# led.net
KiCad netlist of a schematic drawn in EAGLE
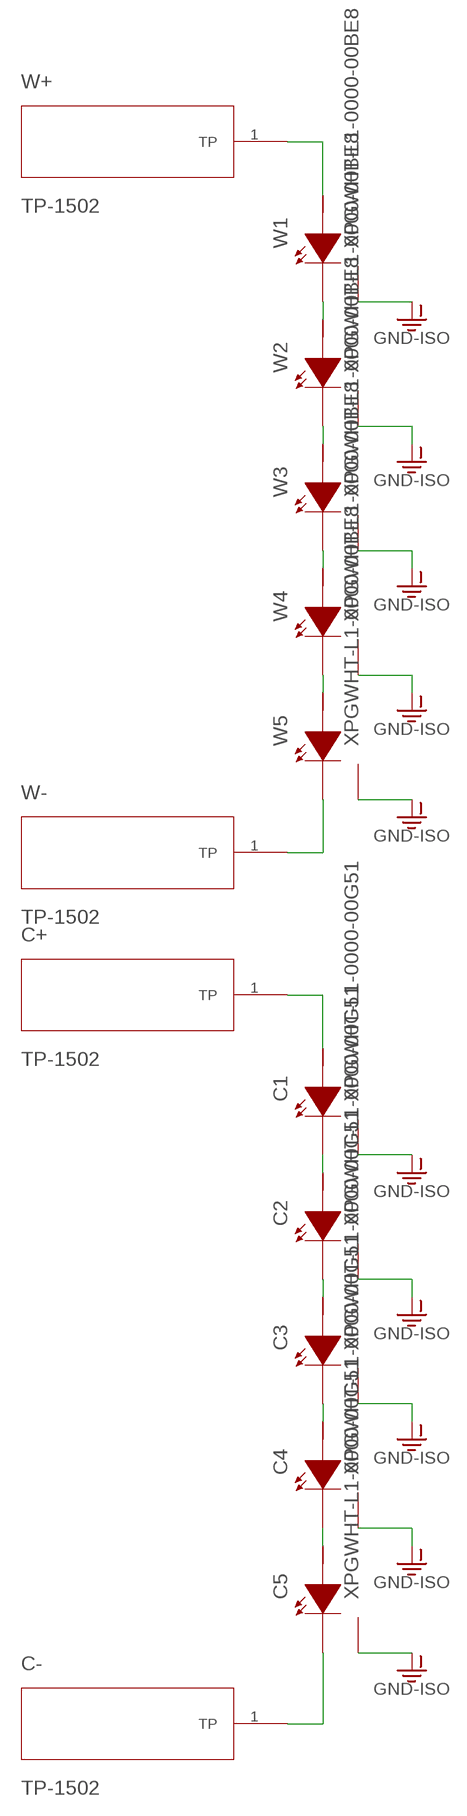
[diagram p0: schematic, sheet 1]

(export (version "E")
  (design (tool "Eeschema 10.0.6"))
  (components
    (comp (ref "C+")
      (value "TP-1502")
      (footprint "eagle-import:TP-1502")
      (libsource (lib "eagle-import") (part "TP-1502"))
    )
    (comp (ref "C-")
      (value "TP-1502")
      (footprint "eagle-import:TP-1502")
      (libsource (lib "eagle-import") (part "TP-1502"))
    )
    (comp (ref "C1")
      (value "XPGWHT-L1-0000-00G51")
      (footprint "eagle-import:XLAMP-XPG")
      (fields (field (name "DIGIKEY_PART_NUMBER") "XPGWHT-L1-0000-00G51CT-ND"))
      (libsource (lib "eagle-import") (part "XPGWHT-L1-0000-00G51"))
    )
    (comp (ref "C2")
      (value "XPGWHT-L1-0000-00G51")
      (footprint "eagle-import:XLAMP-XPG")
      (fields (field (name "DIGIKEY_PART_NUMBER") "XPGWHT-L1-0000-00G51CT-ND"))
      (libsource (lib "eagle-import") (part "XPGWHT-L1-0000-00G51"))
    )
    (comp (ref "C3")
      (value "XPGWHT-L1-0000-00G51")
      (footprint "eagle-import:XLAMP-XPG")
      (fields (field (name "DIGIKEY_PART_NUMBER") "XPGWHT-L1-0000-00G51CT-ND"))
      (libsource (lib "eagle-import") (part "XPGWHT-L1-0000-00G51"))
    )
    (comp (ref "C4")
      (value "XPGWHT-L1-0000-00G51")
      (footprint "eagle-import:XLAMP-XPG")
      (fields (field (name "DIGIKEY_PART_NUMBER") "XPGWHT-L1-0000-00G51CT-ND"))
      (libsource (lib "eagle-import") (part "XPGWHT-L1-0000-00G51"))
    )
    (comp (ref "C5")
      (value "XPGWHT-L1-0000-00G51")
      (footprint "eagle-import:XLAMP-XPG")
      (fields (field (name "DIGIKEY_PART_NUMBER") "XPGWHT-L1-0000-00G51CT-ND"))
      (libsource (lib "eagle-import") (part "XPGWHT-L1-0000-00G51"))
    )
    (comp (ref "W+")
      (value "TP-1502")
      (footprint "eagle-import:TP-1502")
      (libsource (lib "eagle-import") (part "TP-1502"))
    )
    (comp (ref "W-")
      (value "TP-1502")
      (footprint "eagle-import:TP-1502")
      (libsource (lib "eagle-import") (part "TP-1502"))
    )
    (comp (ref "W1")
      (value "XPGWHT-L1-0000-00BE8")
      (footprint "eagle-import:XLAMP-XPG")
      (fields (field (name "DIGIKEY_PART_NUMBER") "XPGWHT-L1-0000-00BE8CT-ND"))
      (libsource (lib "eagle-import") (part "XPGWHT-L1-0000-00BE8"))
    )
    (comp (ref "W2")
      (value "XPGWHT-L1-0000-00BE8")
      (footprint "eagle-import:XLAMP-XPG")
      (fields (field (name "DIGIKEY_PART_NUMBER") "XPGWHT-L1-0000-00BE8CT-ND"))
      (libsource (lib "eagle-import") (part "XPGWHT-L1-0000-00BE8"))
    )
    (comp (ref "W3")
      (value "XPGWHT-L1-0000-00BE8")
      (footprint "eagle-import:XLAMP-XPG")
      (fields (field (name "DIGIKEY_PART_NUMBER") "XPGWHT-L1-0000-00BE8CT-ND"))
      (libsource (lib "eagle-import") (part "XPGWHT-L1-0000-00BE8"))
    )
    (comp (ref "W4")
      (value "XPGWHT-L1-0000-00BE8")
      (footprint "eagle-import:XLAMP-XPG")
      (fields (field (name "DIGIKEY_PART_NUMBER") "XPGWHT-L1-0000-00BE8CT-ND"))
      (libsource (lib "eagle-import") (part "XPGWHT-L1-0000-00BE8"))
    )
    (comp (ref "W5")
      (value "XPGWHT-L1-0000-00BE8")
      (footprint "eagle-import:XLAMP-XPG")
      (fields (field (name "DIGIKEY_PART_NUMBER") "XPGWHT-L1-0000-00BE8CT-ND"))
      (libsource (lib "eagle-import") (part "XPGWHT-L1-0000-00BE8"))
    )
  )
  (nets
    (net (code "1") (name "GND-ISO") (class "Default")
      (node (ref "C1") (pin "GND") (pinfunction "GND_GND") (pintype "passive"))
      (node (ref "C1") (pin "P$1") (pinfunction "GND_P$1") (pintype "passive"))
      (node (ref "C1") (pin "P$2") (pinfunction "GND_P$2") (pintype "passive"))
      (node (ref "C1") (pin "P$3") (pinfunction "GND_P$3") (pintype "passive"))
      (node (ref "C2") (pin "GND") (pinfunction "GND_GND") (pintype "passive"))
      (node (ref "C2") (pin "P$1") (pinfunction "GND_P$1") (pintype "passive"))
      (node (ref "C2") (pin "P$2") (pinfunction "GND_P$2") (pintype "passive"))
      (node (ref "C2") (pin "P$3") (pinfunction "GND_P$3") (pintype "passive"))
      (node (ref "C3") (pin "GND") (pinfunction "GND_GND") (pintype "passive"))
      (node (ref "C3") (pin "P$1") (pinfunction "GND_P$1") (pintype "passive"))
      (node (ref "C3") (pin "P$2") (pinfunction "GND_P$2") (pintype "passive"))
      (node (ref "C3") (pin "P$3") (pinfunction "GND_P$3") (pintype "passive"))
      (node (ref "C4") (pin "GND") (pinfunction "GND_GND") (pintype "passive"))
      (node (ref "C4") (pin "P$1") (pinfunction "GND_P$1") (pintype "passive"))
      (node (ref "C4") (pin "P$2") (pinfunction "GND_P$2") (pintype "passive"))
      (node (ref "C4") (pin "P$3") (pinfunction "GND_P$3") (pintype "passive"))
      (node (ref "C5") (pin "GND") (pinfunction "GND_GND") (pintype "passive"))
      (node (ref "C5") (pin "P$1") (pinfunction "GND_P$1") (pintype "passive"))
      (node (ref "C5") (pin "P$2") (pinfunction "GND_P$2") (pintype "passive"))
      (node (ref "C5") (pin "P$3") (pinfunction "GND_P$3") (pintype "passive"))
      (node (ref "W1") (pin "GND") (pinfunction "GND_GND") (pintype "passive"))
      (node (ref "W1") (pin "P$1") (pinfunction "GND_P$1") (pintype "passive"))
      (node (ref "W1") (pin "P$2") (pinfunction "GND_P$2") (pintype "passive"))
      (node (ref "W1") (pin "P$3") (pinfunction "GND_P$3") (pintype "passive"))
      (node (ref "W2") (pin "GND") (pinfunction "GND_GND") (pintype "passive"))
      (node (ref "W2") (pin "P$1") (pinfunction "GND_P$1") (pintype "passive"))
      (node (ref "W2") (pin "P$2") (pinfunction "GND_P$2") (pintype "passive"))
      (node (ref "W2") (pin "P$3") (pinfunction "GND_P$3") (pintype "passive"))
      (node (ref "W3") (pin "GND") (pinfunction "GND_GND") (pintype "passive"))
      (node (ref "W3") (pin "P$1") (pinfunction "GND_P$1") (pintype "passive"))
      (node (ref "W3") (pin "P$2") (pinfunction "GND_P$2") (pintype "passive"))
      (node (ref "W3") (pin "P$3") (pinfunction "GND_P$3") (pintype "passive"))
      (node (ref "W4") (pin "GND") (pinfunction "GND_GND") (pintype "passive"))
      (node (ref "W4") (pin "P$1") (pinfunction "GND_P$1") (pintype "passive"))
      (node (ref "W4") (pin "P$2") (pinfunction "GND_P$2") (pintype "passive"))
      (node (ref "W4") (pin "P$3") (pinfunction "GND_P$3") (pintype "passive"))
      (node (ref "W5") (pin "GND") (pinfunction "GND_GND") (pintype "passive"))
      (node (ref "W5") (pin "P$1") (pinfunction "GND_P$1") (pintype "passive"))
      (node (ref "W5") (pin "P$2") (pinfunction "GND_P$2") (pintype "passive"))
      (node (ref "W5") (pin "P$3") (pinfunction "GND_P$3") (pintype "passive"))
    )
    (net (code "2") (name "Net-(C+-TP)") (class "Default")
      (node (ref "C+") (pin "1") (pinfunction "TP_1") (pintype "passive"))
      (node (ref "C1") (pin "A") (pinfunction "A_A") (pintype "passive"))
    )
    (net (code "3") (name "Net-(C--TP)") (class "Default")
      (node (ref "C-") (pin "1") (pinfunction "TP_1") (pintype "passive"))
      (node (ref "C5") (pin "C") (pinfunction "C_C") (pintype "passive"))
    )
    (net (code "4") (name "Net-(C1-PadC)") (class "Default")
      (node (ref "C1") (pin "C") (pinfunction "C_C") (pintype "passive"))
      (node (ref "C2") (pin "A") (pinfunction "A_A") (pintype "passive"))
    )
    (net (code "5") (name "Net-(C2-PadC)") (class "Default")
      (node (ref "C2") (pin "C") (pinfunction "C_C") (pintype "passive"))
      (node (ref "C3") (pin "A") (pinfunction "A_A") (pintype "passive"))
    )
    (net (code "6") (name "Net-(C3-PadC)") (class "Default")
      (node (ref "C3") (pin "C") (pinfunction "C_C") (pintype "passive"))
      (node (ref "C4") (pin "A") (pinfunction "A_A") (pintype "passive"))
    )
    (net (code "7") (name "Net-(C4-PadC)") (class "Default")
      (node (ref "C4") (pin "C") (pinfunction "C_C") (pintype "passive"))
      (node (ref "C5") (pin "A") (pinfunction "A_A") (pintype "passive"))
    )
    (net (code "8") (name "Net-(W+-TP)") (class "Default")
      (node (ref "W+") (pin "1") (pinfunction "TP_1") (pintype "passive"))
      (node (ref "W1") (pin "A") (pinfunction "A_A") (pintype "passive"))
    )
    (net (code "9") (name "Net-(W--TP)") (class "Default")
      (node (ref "W-") (pin "1") (pinfunction "TP_1") (pintype "passive"))
      (node (ref "W5") (pin "C") (pinfunction "C_C") (pintype "passive"))
    )
    (net (code "10") (name "Net-(W1-PadC)") (class "Default")
      (node (ref "W1") (pin "C") (pinfunction "C_C") (pintype "passive"))
      (node (ref "W2") (pin "A") (pinfunction "A_A") (pintype "passive"))
    )
    (net (code "11") (name "Net-(W2-PadC)") (class "Default")
      (node (ref "W2") (pin "C") (pinfunction "C_C") (pintype "passive"))
      (node (ref "W3") (pin "A") (pinfunction "A_A") (pintype "passive"))
    )
    (net (code "12") (name "Net-(W3-PadC)") (class "Default")
      (node (ref "W3") (pin "C") (pinfunction "C_C") (pintype "passive"))
      (node (ref "W4") (pin "A") (pinfunction "A_A") (pintype "passive"))
    )
    (net (code "13") (name "Net-(W4-PadC)") (class "Default")
      (node (ref "W4") (pin "C") (pinfunction "C_C") (pintype "passive"))
      (node (ref "W5") (pin "A") (pinfunction "A_A") (pintype "passive"))
    )
  )
)
